# cSLIM-SA_RS232.net
KiCad netlist of a schematic drawn in Altium Designer
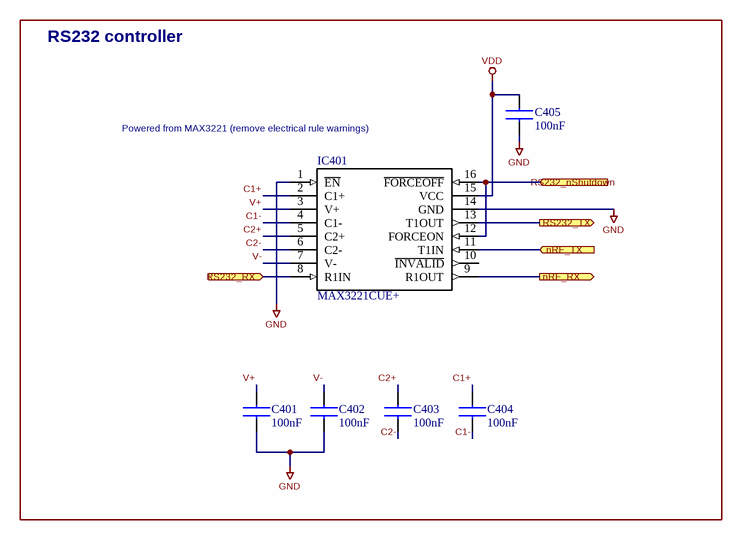
[diagram p0: cSLIM-SA_RS232.SchDoc]

(export (version "E")
  (design (tool "Eeschema 10.0.6"))
  (components
    (comp (ref "C401")
      (value "100nF")
      (footprint "cSLIM-SA:CAPC1608X90N")
      (description "Capacitor")
      (fields
        (field (name "MANUFACTURER_PART_NUMBER") "06033G104ZAT2A")
        (field (name "MOUSER PART NUMBER") "581-06033G104Z")
      )
      (libsource (lib "cSLIM-SA") (part "C"))
    )
    (comp (ref "C402")
      (value "100nF")
      (footprint "cSLIM-SA:CAPC1608X90N")
      (description "Capacitor")
      (fields
        (field (name "MANUFACTURER_PART_NUMBER") "06033G104ZAT2A")
        (field (name "MOUSER PART NUMBER") "581-06033G104Z")
      )
      (libsource (lib "cSLIM-SA") (part "C"))
    )
    (comp (ref "C403")
      (value "100nF")
      (footprint "cSLIM-SA:CAPC1608X90N")
      (description "Capacitor")
      (fields
        (field (name "MANUFACTURER_PART_NUMBER") "06033G104ZAT2A")
        (field (name "MOUSER PART NUMBER") "581-06033G104Z")
      )
      (libsource (lib "cSLIM-SA") (part "C"))
    )
    (comp (ref "C404")
      (value "100nF")
      (footprint "cSLIM-SA:CAPC1608X90N")
      (description "Capacitor")
      (fields
        (field (name "MANUFACTURER_PART_NUMBER") "06033G104ZAT2A")
        (field (name "MOUSER PART NUMBER") "581-06033G104Z")
      )
      (libsource (lib "cSLIM-SA") (part "C"))
    )
    (comp (ref "C405")
      (value "100nF")
      (footprint "cSLIM-SA:CAPC1608X90N")
      (description "Capacitor")
      (fields
        (field (name "MANUFACTURER_PART_NUMBER") "06033G104ZAT2A")
        (field (name "MOUSER PART NUMBER") "581-06033G104Z")
      )
      (libsource (lib "cSLIM-SA") (part "C"))
    )
    (comp (ref "IC401")
      (value "MAX3221CUE+")
      (footprint "cSLIM-SA:SOP65P640X110-16N")
      (description "Integrated Circuit")
      (fields (field (name "MOUSER PART NUMBER") "700-MAX3221CUE"))
      (libsource (lib "cSLIM-SA") (part "MAX3221CUE+"))
    )
  )
  (nets
    (net (code "1") (name "/C1+") (class "Default")
      (node (ref "C404") (pin "1") (pinfunction "1_1") (pintype "passive"))
      (node (ref "IC401") (pin "2") (pinfunction "C1+_2") (pintype "passive"))
    )
    (net (code "2") (name "/C1-") (class "Default")
      (node (ref "C404") (pin "2") (pinfunction "2_2") (pintype "passive"))
      (node (ref "IC401") (pin "4") (pinfunction "C1-_4") (pintype "passive"))
    )
    (net (code "3") (name "/C2+") (class "Default")
      (node (ref "C403") (pin "1") (pinfunction "1_1") (pintype "passive"))
      (node (ref "IC401") (pin "5") (pinfunction "C2+_5") (pintype "passive"))
    )
    (net (code "4") (name "/C2-") (class "Default")
      (node (ref "C403") (pin "2") (pinfunction "2_2") (pintype "passive"))
      (node (ref "IC401") (pin "6") (pinfunction "C2-_6") (pintype "passive"))
    )
    (net (code "5") (name "/RS232_RX") (class "Default")
      (node (ref "IC401") (pin "8") (pinfunction "R1IN_8") (pintype "input"))
    )
    (net (code "6") (name "/RS232_TX") (class "Default")
      (node (ref "IC401") (pin "13") (pinfunction "T1OUT_13") (pintype "output"))
    )
    (net (code "7") (name "/RS232_nShutdown") (class "Default")
      (node (ref "IC401") (pin "12") (pinfunction "FORCEON_12") (pintype "input"))
      (node (ref "IC401") (pin "16") (pinfunction "~{FORCEOFF}_16") (pintype "input"))
    )
    (net (code "8") (name "/V+") (class "Default")
      (node (ref "C401") (pin "1") (pinfunction "1_1") (pintype "passive"))
      (node (ref "IC401") (pin "3") (pinfunction "V+_3") (pintype "power_in"))
    )
    (net (code "9") (name "/V-") (class "Default")
      (node (ref "C402") (pin "1") (pinfunction "1_1") (pintype "passive"))
      (node (ref "IC401") (pin "7") (pinfunction "V-_7") (pintype "power_in"))
    )
    (net (code "10") (name "/nRF_RX") (class "Default")
      (node (ref "IC401") (pin "9") (pinfunction "R1OUT_9") (pintype "output"))
    )
    (net (code "11") (name "/nRF_TX") (class "Default")
      (node (ref "IC401") (pin "11") (pinfunction "T1IN_11") (pintype "input"))
    )
    (net (code "12") (name "GND") (class "Default")
      (node (ref "C401") (pin "2") (pinfunction "2_2") (pintype "passive"))
      (node (ref "C402") (pin "2") (pinfunction "2_2") (pintype "passive"))
      (node (ref "C405") (pin "2") (pinfunction "2_2") (pintype "passive"))
      (node (ref "IC401") (pin "1") (pinfunction "~{EN}_1") (pintype "input"))
      (node (ref "IC401") (pin "14") (pinfunction "GND_14") (pintype "power_in"))
    )
    (net (code "13") (name "VDD") (class "Default")
      (node (ref "C405") (pin "1") (pinfunction "1_1") (pintype "passive"))
      (node (ref "IC401") (pin "15") (pinfunction "VCC_15") (pintype "power_in"))
    )
    (net (code "14") (name "unconnected-(IC401-~{INVALID}-Pad10)") (class "Default")
      (node (ref "IC401") (pin "10") (pinfunction "~{INVALID}_10") (pintype "output"))
    )
  )
)
